# BLOCK_DIAGRAM.net
KiCad netlist of a schematic drawn in Altium Designer
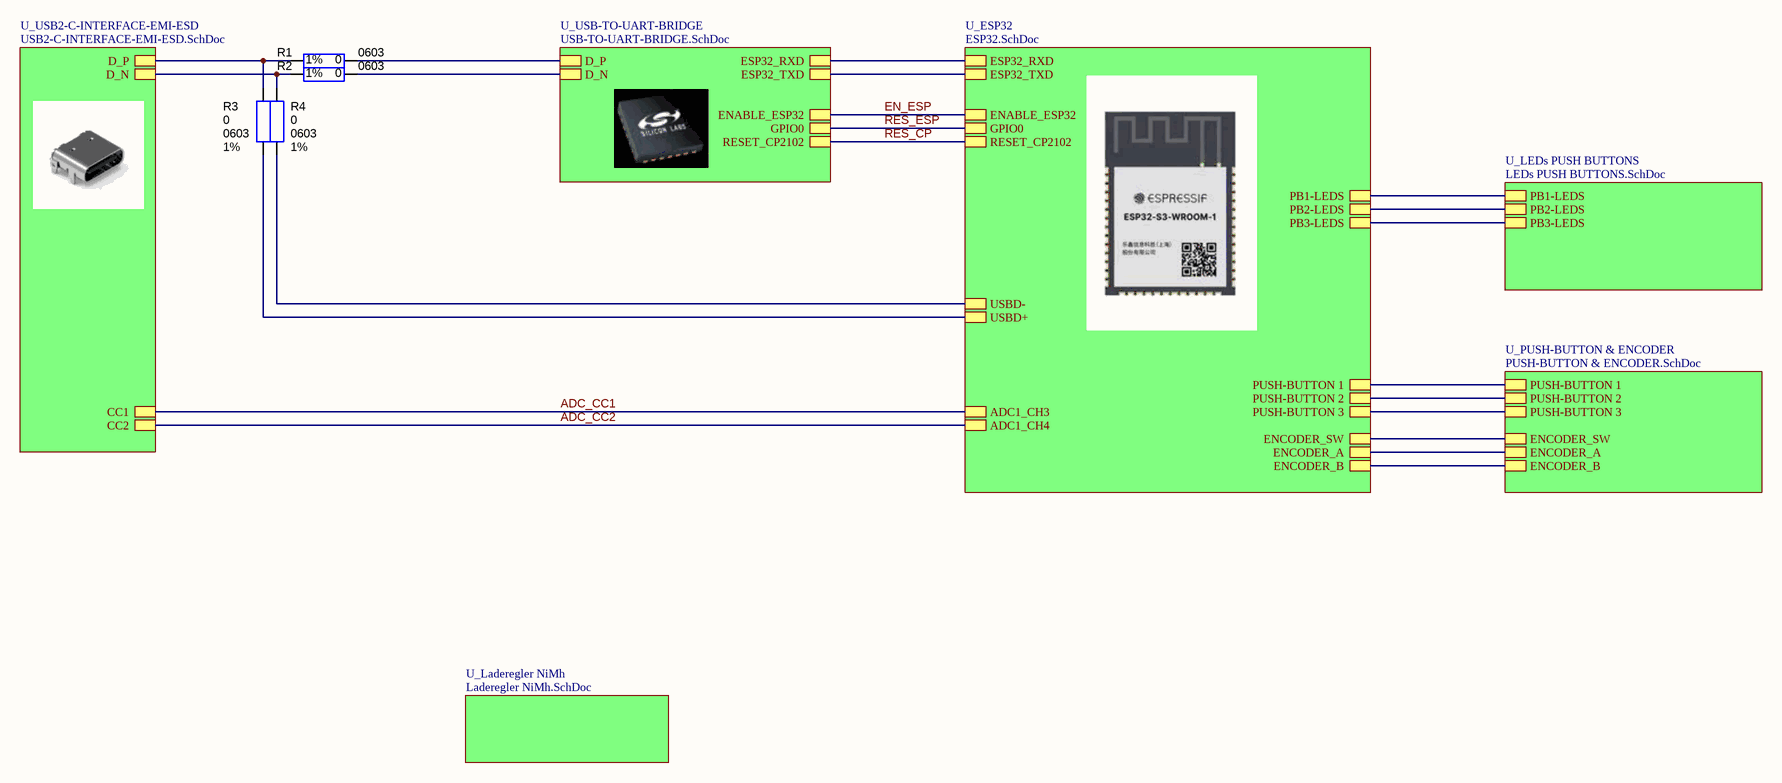
[diagram p0: BLOCK DIAGRAM.SchDoc]

(export (version "E")
  (design (tool "Eeschema 10.0.6"))
  (components
    (comp (ref "R1")
      (value "0")
      (footprint "RESC0603X21L")
      (description "RESISTOR 0R 1% 0603 100mW")
      (fields
        (field (name "MANUFACTURER 1 PART NUMBER") "RC0603FR-070RL")
        (field (name "CASE/PACKAGE") "0603")
        (field (name "POWER") "100mW")
        (field (name "TOLERANCE") "1%")
        (field (name "COMMENT DESIGNER") "can be substituted same values other manufacturers")
      )
      (libsource (lib "EDATRON Solutions GmbH") (part "R"))
    )
    (comp (ref "R2")
      (value "0")
      (footprint "RESC0603X21L")
      (description "RESISTOR 0R 1% 0603 100mW")
      (fields
        (field (name "MANUFACTURER 1 PART NUMBER") "RC0603FR-070RL")
        (field (name "CASE/PACKAGE") "0603")
        (field (name "POWER") "100mW")
        (field (name "TOLERANCE") "1%")
        (field (name "COMMENT DESIGNER") "can be substituted same values other manufacturers")
      )
      (libsource (lib "EDATRON Solutions GmbH") (part "R"))
    )
    (comp (ref "R3")
      (value "0")
      (footprint "RESC0603X21L")
      (description "RESISTOR 0R 1% 0603 100mW")
      (fields
        (field (name "MANUFACTURER 1 PART NUMBER") "RC0603FR-070RL")
        (field (name "CASE/PACKAGE") "0603")
        (field (name "POWER") "100mW")
        (field (name "TOLERANCE") "1%")
        (field (name "COMMENT DESIGNER") "can be substituted same values other manufacturers")
      )
      (libsource (lib "EDATRON Solutions GmbH") (part "R"))
    )
    (comp (ref "R4")
      (value "0")
      (footprint "RESC0603X21L")
      (description "RESISTOR 0R 1% 0603 100mW")
      (fields
        (field (name "MANUFACTURER 1 PART NUMBER") "RC0603FR-070RL")
        (field (name "CASE/PACKAGE") "0603")
        (field (name "POWER") "100mW")
        (field (name "TOLERANCE") "1%")
        (field (name "COMMENT DESIGNER") "can be substituted same values other manufacturers")
      )
      (libsource (lib "") (part "R_1"))
    )
  )
  (nets
    (net (code "3") (name "/D_N") (class "Default")
      (node (ref "R2") (pin "1") (pinfunction "1_1") (pintype "passive"))
      (node (ref "R4") (pin "2") (pinfunction "2_2") (pintype "passive"))
    )
    (net (code "4") (name "/D_N_1") (class "Default")
      (node (ref "R2") (pin "2") (pinfunction "2_2") (pintype "passive"))
    )
    (net (code "5") (name "/D_P") (class "Default")
      (node (ref "R1") (pin "1") (pinfunction "1_1") (pintype "passive"))
      (node (ref "R3") (pin "2") (pinfunction "2_2") (pintype "passive"))
    )
    (net (code "6") (name "/D_P_1") (class "Default")
      (node (ref "R1") (pin "2") (pinfunction "2_2") (pintype "passive"))
    )
    (net (code "21") (name "/USBD+") (class "Default")
      (node (ref "R3") (pin "1") (pinfunction "1_1") (pintype "passive"))
    )
    (net (code "22") (name "/USBD-") (class "Default")
      (node (ref "R4") (pin "1") (pinfunction "1_1") (pintype "passive"))
    )
  )
)
